# quadcopter_tawfic.net
KiCad netlist of a schematic drawn in EAGLE
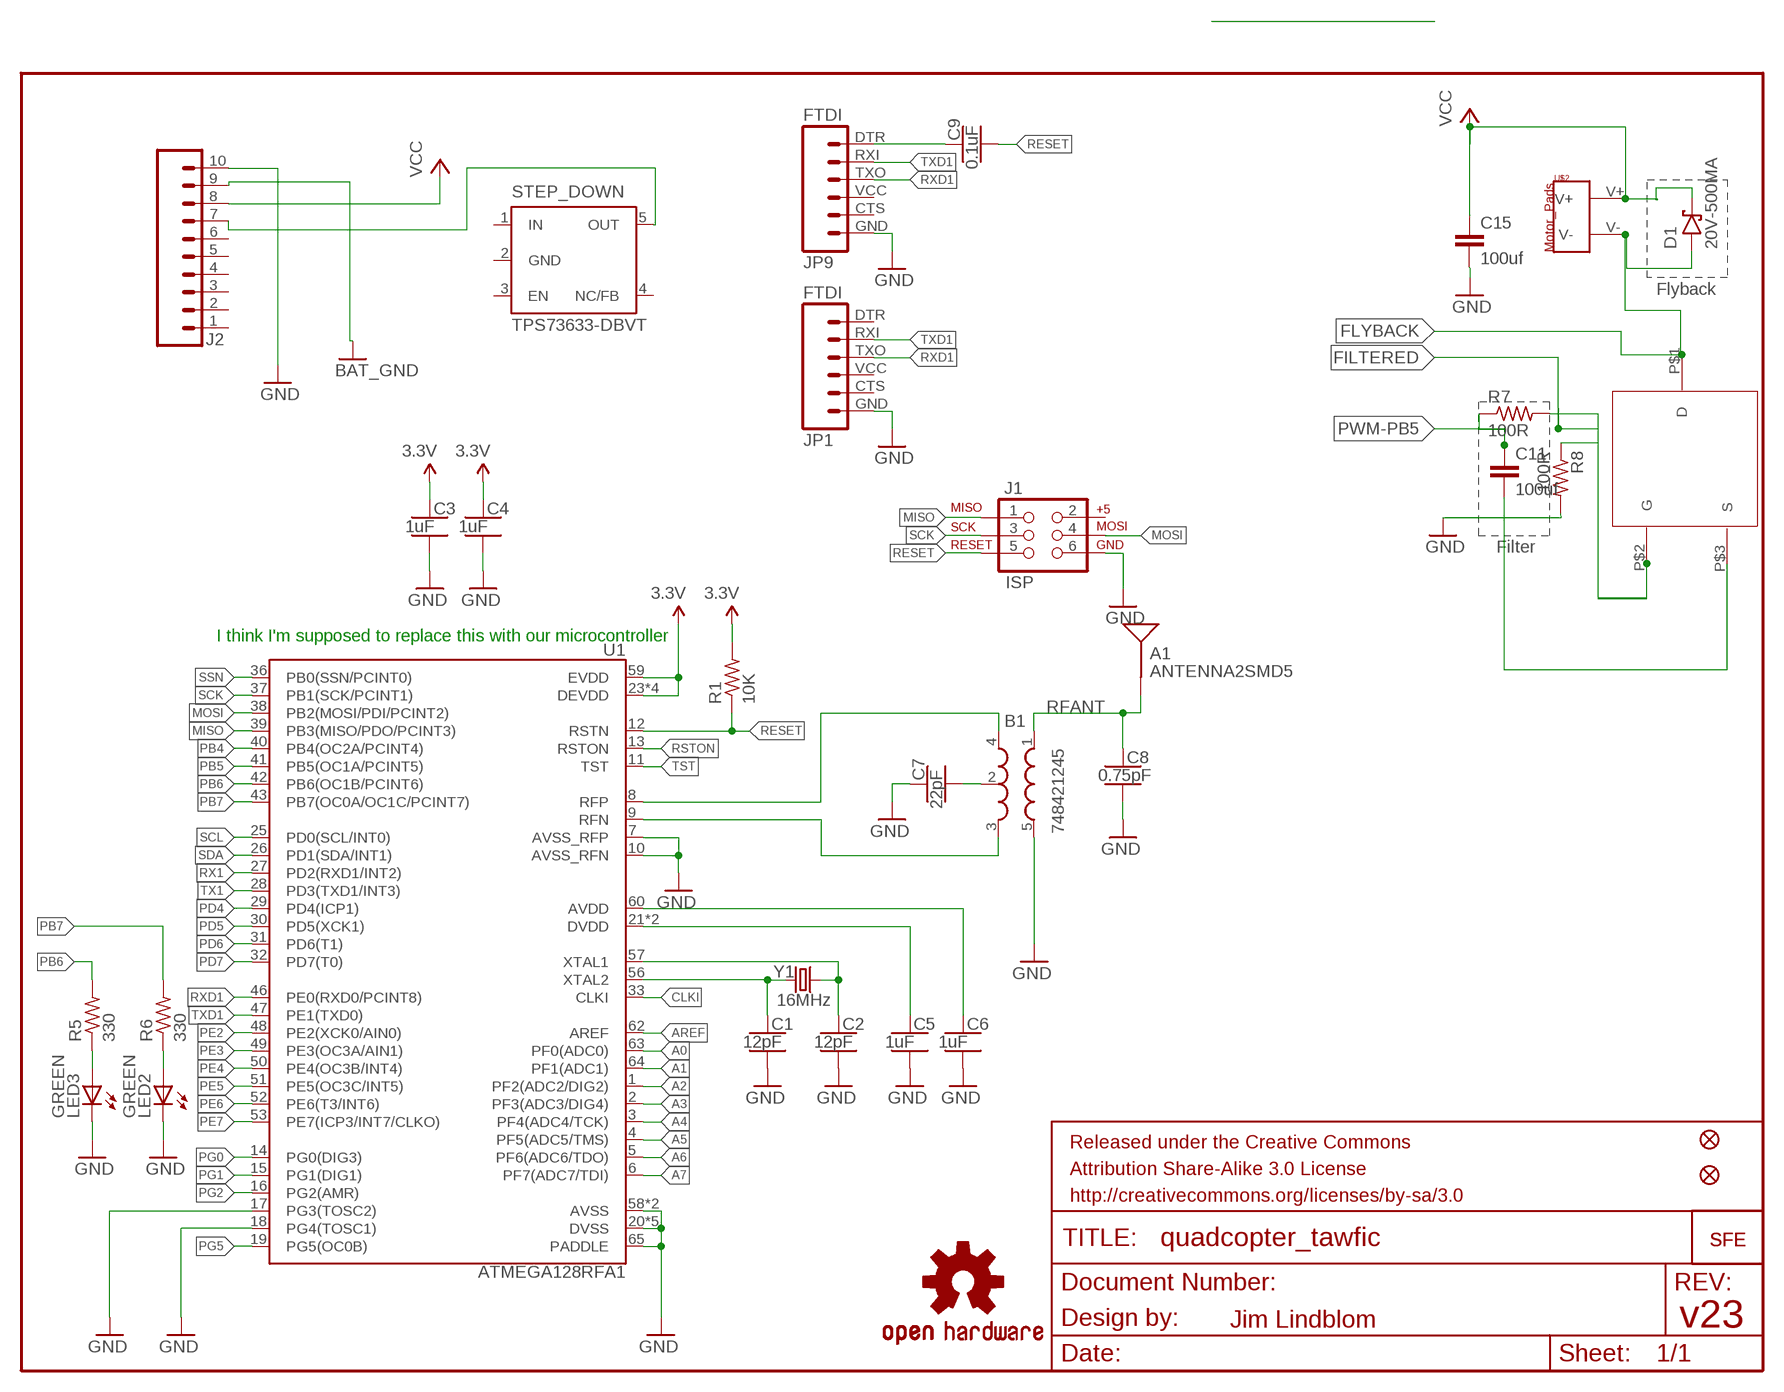
[diagram p0: schematic, sheet 1]

(export (version "E")
  (design (tool "Eeschema 10.0.6"))
  (components
    (comp (ref "A1")
      (value "ANTENNA2SMD5")
      (footprint "eagle-import:ANTENNA-CHIP5")
      (libsource (lib "eagle-import") (part "ANTENNA2SMD5"))
    )
    (comp (ref "B1")
      (value "748421245")
      (footprint "eagle-import:BALUN")
      (libsource (lib "eagle-import") (part "BALUN0805"))
    )
    (comp (ref "C1")
      (value "12pF")
      (footprint "eagle-import:CAPC2012X140_HS")
      (fields
        (field (name "MFR") "Murata Electronics North America")
        (field (name "MPN") "GRM21A5C2E120JW01D")
      )
      (libsource (lib "eagle-import") (part "CAPACITOR-NP_SMD-2012-0805_CERAMIC-12PF"))
    )
    (comp (ref "C2")
      (value "12pF")
      (footprint "eagle-import:CAPC2012X140_HS")
      (fields
        (field (name "MFR") "Murata Electronics North America")
        (field (name "MPN") "GRM21A5C2E120JW01D")
      )
      (libsource (lib "eagle-import") (part "CAPACITOR-NP_SMD-2012-0805_CERAMIC-12PF"))
    )
    (comp (ref "C3")
      (value "1uF")
      (footprint "eagle-import:CAPC2012X140_HS")
      (fields
        (field (name "MFR") "Murata Electronics North America")
        (field (name "MPN") "GRM21BR71H105KA12L")
      )
      (libsource (lib "eagle-import") (part "CAPACITOR-NP_SMD-2012-0805_CERAMIC-1UF"))
    )
    (comp (ref "C4")
      (value "1uF")
      (footprint "eagle-import:CAPC2012X140_HS")
      (fields
        (field (name "MFR") "Murata Electronics North America")
        (field (name "MPN") "GRM21BR71H105KA12L")
      )
      (libsource (lib "eagle-import") (part "CAPACITOR-NP_SMD-2012-0805_CERAMIC-1UF"))
    )
    (comp (ref "C5")
      (value "1uF")
      (footprint "eagle-import:CAPC2012X140_HS")
      (fields
        (field (name "MFR") "Murata Electronics North America")
        (field (name "MPN") "GRM21BR71H105KA12L")
      )
      (libsource (lib "eagle-import") (part "CAPACITOR-NP_SMD-2012-0805_CERAMIC-1UF"))
    )
    (comp (ref "C6")
      (value "1uF")
      (footprint "eagle-import:CAPC2012X140_HS")
      (fields
        (field (name "MFR") "Murata Electronics North America")
        (field (name "MPN") "GRM21BR71H105KA12L")
      )
      (libsource (lib "eagle-import") (part "CAPACITOR-NP_SMD-2012-0805_CERAMIC-1UF"))
    )
    (comp (ref "C7")
      (value "22pF")
      (footprint "eagle-import:CAPC2012X140_HS")
      (fields
        (field (name "MFR") "Murata Electronics North America")
        (field (name "MPN") "GRM21A5C2E220JW01D")
      )
      (libsource (lib "eagle-import") (part "CAPACITOR-NP_SMD-2012-0805_CERAMIC-22PF"))
    )
    (comp (ref "C8")
      (value "0.75pF")
      (footprint "eagle-import:CAPC2012X140_HS")
      (fields
        (field (name "MFR") "Murata Electronics North America")
        (field (name "MPN") "GQM2195C2AR75CB01D")
      )
      (libsource (lib "eagle-import") (part "CAPACITOR-NP_SMD-2012-0805_CERAMIC-0.75PF"))
    )
    (comp (ref "C9")
      (value "0.1uF")
      (footprint "eagle-import:CAPC2012X140_HS")
      (fields
        (field (name "MFR") "Murata Electronics North America")
        (field (name "MPN") "GRM21BR71H104KA01L")
      )
      (libsource (lib "eagle-import") (part "CAPACITOR-NP_SMD-2012-0805_CERAMIC-0.1UF"))
    )
    (comp (ref "C11")
      (value "100uf")
      (footprint "eagle-import:C10B4")
      (libsource (lib "eagle-import") (part "C10/4"))
    )
    (comp (ref "C15")
      (value "100uf")
      (footprint "eagle-import:C10B4")
      (libsource (lib "eagle-import") (part "C10/4"))
    )
    (comp (ref "D1")
      (value "20V-500MA")
      (footprint "eagle-import:SOD3716X135_HS")
      (fields
        (field (name "MFR") "Toshiba Semiconductor and Storage")
        (field (name "MPN") "CRS08(TE85L,Q,M)")
      )
      (libsource (lib "eagle-import") (part "DIODE-SCHOTTKY_SMD-SOD123-360MV"))
    )
    (comp (ref "FID1")
      (value "FIDUCIALUFIDUCIAL")
      (footprint "eagle-import:MICRO-FIDUCIAL")
      (libsource (lib "eagle-import") (part "FIDUCIALUFIDUCIAL"))
    )
    (comp (ref "FID2")
      (value "FIDUCIALUFIDUCIAL")
      (footprint "eagle-import:MICRO-FIDUCIAL")
      (libsource (lib "eagle-import") (part "FIDUCIALUFIDUCIAL"))
    )
    (comp (ref "J1")
      (value "ISP")
      (footprint "eagle-import:2X3-NS")
      (libsource (lib "eagle-import") (part "AVR_SPI_PRG_6NS"))
    )
    (comp (ref "J2")
      (value "SIP-10_TH-254X10-1")
      (footprint "eagle-import:HDRV10W63P254_10X1_2540X254H838_HS")
      (fields (field (name "MFR") "Amphenol FCI") (field (name "MPN") "68000-110HLF"))
      (libsource (lib "eagle-import") (part "SIP-10_TH-254X10-1"))
    )
    (comp (ref "JP1")
      (value "FTDI")
      (footprint "eagle-import:FTDI_BASIC")
      (libsource (lib "eagle-import") (part "FTDI_BASICPTH"))
    )
    (comp (ref "JP4")
      (value "LOGO-SFENEW")
      (footprint "eagle-import:SFE-NEW-WEBLOGO")
      (libsource (lib "eagle-import") (part "LOGO-SFENEW"))
    )
    (comp (ref "JP9")
      (value "FTDI")
      (footprint "eagle-import:FTDI_BASIC")
      (libsource (lib "eagle-import") (part "FTDI_BASICPTH"))
    )
    (comp (ref "JP10")
      (value "LOGO-SFENEW")
      (footprint "eagle-import:SFE-NEW-WEBLOGO")
      (libsource (lib "eagle-import") (part "LOGO-SFENEW"))
    )
    (comp (ref "LED2")
      (value "GREEN")
      (footprint "eagle-import:LED-0603")
      (libsource (lib "eagle-import") (part "LED0603"))
    )
    (comp (ref "LED3")
      (value "GREEN")
      (footprint "eagle-import:LED-0603")
      (libsource (lib "eagle-import") (part "LED0603"))
    )
    (comp (ref "Q2")
      (value "MOSFET-SI2302CDS-T1-E3")
      (footprint "eagle-import:MOSFET")
      (libsource (lib "eagle-import") (part "MOSFET-SI2302CDS-T1-E3"))
    )
    (comp (ref "R1")
      (value "10K")
      (footprint "eagle-import:RESC2012X60_HS")
      (fields (field (name "MFR") "Yageo") (field (name "MPN") "RC0805JR-0710KL"))
      (libsource (lib "eagle-import") (part "RESISTOR_SMD-2012-0805-10K"))
    )
    (comp (ref "R5")
      (value "330")
      (footprint "eagle-import:RESC2012X60_HS")
      (fields (field (name "MFR") "Yageo") (field (name "MPN") "RC0805JR-07330RL"))
      (libsource (lib "eagle-import") (part "RESISTOR_SMD-2012-0805-330"))
    )
    (comp (ref "R6")
      (value "330")
      (footprint "eagle-import:RESC2012X60_HS")
      (fields (field (name "MFR") "Yageo") (field (name "MPN") "RC0805JR-07330RL"))
      (libsource (lib "eagle-import") (part "RESISTOR_SMD-2012-0805-330"))
    )
    (comp (ref "R7")
      (value "100R")
      (footprint "eagle-import:R0805")
      (libsource (lib "eagle-import") (part "R-US_R0805"))
    )
    (comp (ref "R8")
      (value "100R")
      (footprint "eagle-import:R0805")
      (libsource (lib "eagle-import") (part "R-US_R0805"))
    )
    (comp (ref "STEP_DOWN")
      (value "TPS73633-DBVT")
      (footprint "eagle-import:SOT23-DBV")
      (fields (field (name "MFR") "Texas Instruments") (field (name "MPN") "LP3985IM5X-3.0/NOPB"))
      (libsource (lib "eagle-import") (part "TPS73633-DBVT"))
    )
    (comp (ref "U$1")
      (value "OSHW-LOGOS")
      (footprint "eagle-import:OSHW-LOGO-S")
      (libsource (lib "eagle-import") (part "OSHW-LOGOS"))
    )
    (comp (ref "U$2")
      (value "MOTOR_PADS")
      (footprint "eagle-import:MOTOR_PADS")
      (fields (field (name "MFR") "NA"))
      (libsource (lib "eagle-import") (part "MOTOR_PADS"))
    )
    (comp (ref "U1")
      (value "ATMEGA128RFA1")
      (footprint "eagle-import:QFN-64")
      (libsource (lib "eagle-import") (part "ATMEGA128RFA1"))
    )
    (comp (ref "Y1")
      (value "16MHz")
      (footprint "eagle-import:CRYSTAL-SMD-5X3")
      (libsource (lib "eagle-import") (part "CRYSTAL5X3"))
    )
  )
  (nets
    (net (code "1") (name "/RFANT") (class "Default")
      (node (ref "A1") (pin "FEED") (pinfunction "SIGNAL_FEED") (pintype "bidirectional"))
      (node (ref "B1") (pin "1") (pinfunction "IN_1") (pintype "bidirectional"))
      (node (ref "C8") (pin "1") (pinfunction "1_1") (pintype "passive"))
    )
    (net (code "2") (name "3.3V") (class "Default")
      (node (ref "C3") (pin "1") (pinfunction "1_1") (pintype "passive"))
      (node (ref "C4") (pin "1") (pinfunction "1_1") (pintype "passive"))
      (node (ref "R1") (pin "2") (pinfunction "2_2") (pintype "passive"))
      (node (ref "U1") (pin "23") (pinfunction "DEVDD_23") (pintype "bidirectional"))
      (node (ref "U1") (pin "34") (pinfunction "DEVDD_34") (pintype "bidirectional"))
      (node (ref "U1") (pin "44") (pinfunction "DEVDD_44") (pintype "bidirectional"))
      (node (ref "U1") (pin "54") (pinfunction "DEVDD_54") (pintype "bidirectional"))
      (node (ref "U1") (pin "59") (pinfunction "EVDD_59") (pintype "bidirectional"))
    )
    (net (code "3") (name "A0") (class "Default")
      (node (ref "U1") (pin "63") (pinfunction "PF0(ADC0)_63") (pintype "bidirectional"))
    )
    (net (code "4") (name "A1") (class "Default")
      (node (ref "U1") (pin "64") (pinfunction "PF1(ADC1)_64") (pintype "bidirectional"))
    )
    (net (code "5") (name "A2") (class "Default")
      (node (ref "U1") (pin "1") (pinfunction "PF2(ADC2/DIG2)_1") (pintype "bidirectional"))
    )
    (net (code "6") (name "A3") (class "Default")
      (node (ref "U1") (pin "2") (pinfunction "PF3(ADC3/DIG4)_2") (pintype "bidirectional"))
    )
    (net (code "7") (name "A4") (class "Default")
      (node (ref "U1") (pin "3") (pinfunction "PF4(ADC4/TCK)_3") (pintype "bidirectional"))
    )
    (net (code "8") (name "A5") (class "Default")
      (node (ref "U1") (pin "4") (pinfunction "PF5(ADC5/TMS)_4") (pintype "bidirectional"))
    )
    (net (code "9") (name "A6") (class "Default")
      (node (ref "U1") (pin "5") (pinfunction "PF6(ADC6/TDO)_5") (pintype "bidirectional"))
    )
    (net (code "10") (name "A7") (class "Default")
      (node (ref "U1") (pin "6") (pinfunction "PF7(ADC7/TDI)_6") (pintype "bidirectional"))
    )
    (net (code "11") (name "AREF") (class "Default")
      (node (ref "U1") (pin "62") (pinfunction "AREF_62") (pintype "bidirectional"))
    )
    (net (code "12") (name "BAT_GND") (class "Default")
      (node (ref "J2") (pin "9") (pinfunction "9_9") (pintype "passive"))
    )
    (net (code "13") (name "CLKI") (class "Default")
      (node (ref "U1") (pin "33") (pinfunction "CLKI_33") (pintype "bidirectional"))
    )
    (net (code "14") (name "FILTERED") (class "Default")
      (node (ref "Q2") (pin "P$2") (pinfunction "G_P$2") (pintype "power_in"))
      (node (ref "R7") (pin "2") (pinfunction "2_2") (pintype "passive"))
      (node (ref "R8") (pin "1") (pinfunction "1_1") (pintype "passive"))
    )
    (net (code "15") (name "FLYBACK") (class "Default")
      (node (ref "D1") (pin "A") (pinfunction "A_A") (pintype "passive"))
      (node (ref "Q2") (pin "P$1") (pinfunction "D_P$1") (pintype "bidirectional"))
      (node (ref "U$2") (pin "V-") (pinfunction "V-_V-") (pintype "bidirectional"))
    )
    (net (code "16") (name "GND") (class "Default")
      (node (ref "B1") (pin "5") (pinfunction "GND_5") (pintype "bidirectional"))
      (node (ref "C1") (pin "2") (pinfunction "2_2") (pintype "passive"))
      (node (ref "C15") (pin "2") (pinfunction "2_2") (pintype "passive"))
      (node (ref "C2") (pin "2") (pinfunction "2_2") (pintype "passive"))
      (node (ref "C3") (pin "2") (pinfunction "2_2") (pintype "passive"))
      (node (ref "C4") (pin "2") (pinfunction "2_2") (pintype "passive"))
      (node (ref "C5") (pin "2") (pinfunction "2_2") (pintype "passive"))
      (node (ref "C6") (pin "2") (pinfunction "2_2") (pintype "passive"))
      (node (ref "C7") (pin "1") (pinfunction "1_1") (pintype "passive"))
      (node (ref "C8") (pin "2") (pinfunction "2_2") (pintype "passive"))
      (node (ref "J1") (pin "6") (pinfunction "6_6") (pintype "passive"))
      (node (ref "J2") (pin "10") (pinfunction "10_10") (pintype "passive"))
      (node (ref "JP1") (pin "GND") (pinfunction "6_GND") (pintype "passive"))
      (node (ref "JP9") (pin "GND") (pinfunction "6_GND") (pintype "passive"))
      (node (ref "LED2") (pin "C") (pinfunction "C_C") (pintype "passive"))
      (node (ref "LED3") (pin "C") (pinfunction "C_C") (pintype "passive"))
      (node (ref "R8") (pin "2") (pinfunction "2_2") (pintype "passive"))
      (node (ref "U1") (pin "10") (pinfunction "AVSS_RFN_10") (pintype "bidirectional"))
      (node (ref "U1") (pin "17") (pinfunction "PG3(TOSC2)_17") (pintype "bidirectional"))
      (node (ref "U1") (pin "18") (pinfunction "PG4(TOSC1)_18") (pintype "bidirectional"))
      (node (ref "U1") (pin "20") (pinfunction "DVSS_20") (pintype "bidirectional"))
      (node (ref "U1") (pin "24") (pinfunction "DVSS_24") (pintype "bidirectional"))
      (node (ref "U1") (pin "35") (pinfunction "DVSS_35") (pintype "bidirectional"))
      (node (ref "U1") (pin "45") (pinfunction "DVSS_45") (pintype "bidirectional"))
      (node (ref "U1") (pin "55") (pinfunction "DVSS_55") (pintype "bidirectional"))
      (node (ref "U1") (pin "58") (pinfunction "AVSS_58") (pintype "bidirectional"))
      (node (ref "U1") (pin "61") (pinfunction "AVSS_61") (pintype "bidirectional"))
      (node (ref "U1") (pin "65") (pinfunction "PADDLE_65") (pintype "bidirectional"))
      (node (ref "U1") (pin "7") (pinfunction "AVSS_RFP_7") (pintype "bidirectional"))
    )
    (net (code "17") (name "MISO") (class "Default")
      (node (ref "J1") (pin "1") (pinfunction "1_1") (pintype "passive"))
      (node (ref "U1") (pin "39") (pinfunction "PB3(MISO/PDO/PCINT3)_39") (pintype "bidirectional"))
    )
    (net (code "18") (name "MOSI") (class "Default")
      (node (ref "J1") (pin "4") (pinfunction "4_4") (pintype "passive"))
      (node (ref "U1") (pin "38") (pinfunction "PB2(MOSI/PDI/PCINT2)_38") (pintype "bidirectional"))
    )
    (net (code "19") (name "Net-(B1-GND-Pad2)") (class "Default")
      (node (ref "B1") (pin "2") (pinfunction "GND_2") (pintype "bidirectional"))
      (node (ref "C7") (pin "2") (pinfunction "2_2") (pintype "passive"))
    )
    (net (code "20") (name "Net-(B1-OUT1)") (class "Default")
      (node (ref "B1") (pin "4") (pinfunction "OUT1_4") (pintype "bidirectional"))
      (node (ref "U1") (pin "8") (pinfunction "RFP_8") (pintype "bidirectional"))
    )
    (net (code "21") (name "Net-(B1-OUT2)") (class "Default")
      (node (ref "B1") (pin "3") (pinfunction "OUT2_3") (pintype "bidirectional"))
      (node (ref "U1") (pin "9") (pinfunction "RFN_9") (pintype "bidirectional"))
    )
    (net (code "22") (name "Net-(C5-Pad1)") (class "Default")
      (node (ref "C5") (pin "1") (pinfunction "1_1") (pintype "passive"))
      (node (ref "U1") (pin "21") (pinfunction "DVDD_21") (pintype "bidirectional"))
      (node (ref "U1") (pin "22") (pinfunction "DVDD_22") (pintype "bidirectional"))
    )
    (net (code "23") (name "Net-(JP9-1)") (class "Default")
      (node (ref "C9") (pin "1") (pinfunction "1_1") (pintype "passive"))
      (node (ref "JP9") (pin "DTR") (pinfunction "1_DTR") (pintype "passive"))
    )
    (net (code "24") (name "Net-(LED2-PadA)") (class "Default")
      (node (ref "LED2") (pin "A") (pinfunction "A_A") (pintype "passive"))
      (node (ref "R6") (pin "1") (pinfunction "1_1") (pintype "passive"))
    )
    (net (code "25") (name "Net-(LED3-PadA)") (class "Default")
      (node (ref "LED3") (pin "A") (pinfunction "A_A") (pintype "passive"))
      (node (ref "R5") (pin "1") (pinfunction "1_1") (pintype "passive"))
    )
    (net (code "26") (name "Net-(Q2-S)") (class "Default")
      (node (ref "C11") (pin "2") (pinfunction "2_2") (pintype "passive"))
      (node (ref "Q2") (pin "P$3") (pinfunction "S_P$3") (pintype "bidirectional"))
    )
    (net (code "27") (name "Net-(STEP_DOWN-OUT)") (class "Default")
      (node (ref "J2") (pin "7") (pinfunction "7_7") (pintype "passive"))
      (node (ref "STEP_DOWN") (pin "5") (pinfunction "OUT_5") (pintype "passive"))
    )
    (net (code "28") (name "Net-(U1-AVDD)") (class "Default")
      (node (ref "C6") (pin "1") (pinfunction "1_1") (pintype "passive"))
      (node (ref "U1") (pin "60") (pinfunction "AVDD_60") (pintype "bidirectional"))
    )
    (net (code "29") (name "Net-(U1-XTAL1)") (class "Default")
      (node (ref "C2") (pin "1") (pinfunction "1_1") (pintype "passive"))
      (node (ref "U1") (pin "57") (pinfunction "XTAL1_57") (pintype "bidirectional"))
      (node (ref "Y1") (pin "3") (pinfunction "2_3") (pintype "passive"))
    )
    (net (code "30") (name "Net-(U1-XTAL2)") (class "Default")
      (node (ref "C1") (pin "1") (pinfunction "1_1") (pintype "passive"))
      (node (ref "U1") (pin "56") (pinfunction "XTAL2_56") (pintype "bidirectional"))
      (node (ref "Y1") (pin "1") (pinfunction "1_1") (pintype "passive"))
    )
    (net (code "31") (name "PB4") (class "Default")
      (node (ref "U1") (pin "40") (pinfunction "PB4(OC2A/PCINT4)_40") (pintype "bidirectional"))
    )
    (net (code "32") (name "PB5") (class "Default")
      (node (ref "U1") (pin "41") (pinfunction "PB5(OC1A/PCINT5)_41") (pintype "bidirectional"))
    )
    (net (code "33") (name "PB6") (class "Default")
      (node (ref "R5") (pin "2") (pinfunction "2_2") (pintype "passive"))
      (node (ref "U1") (pin "42") (pinfunction "PB6(OC1B/PCINT6)_42") (pintype "bidirectional"))
    )
    (net (code "34") (name "PB7") (class "Default")
      (node (ref "R6") (pin "2") (pinfunction "2_2") (pintype "passive"))
      (node (ref "U1") (pin "43") (pinfunction "PB7(OC0A/OC1C/PCINT7)_43") (pintype "bidirectional"))
    )
    (net (code "35") (name "PD4") (class "Default")
      (node (ref "U1") (pin "29") (pinfunction "PD4(ICP1)_29") (pintype "bidirectional"))
    )
    (net (code "36") (name "PD5") (class "Default")
      (node (ref "U1") (pin "30") (pinfunction "PD5(XCK1)_30") (pintype "bidirectional"))
    )
    (net (code "37") (name "PD6") (class "Default")
      (node (ref "U1") (pin "31") (pinfunction "PD6(T1)_31") (pintype "bidirectional"))
    )
    (net (code "38") (name "PD7") (class "Default")
      (node (ref "U1") (pin "32") (pinfunction "PD7(T0)_32") (pintype "bidirectional"))
    )
    (net (code "39") (name "PE2") (class "Default")
      (node (ref "U1") (pin "48") (pinfunction "PE2(XCK0/AIN0)_48") (pintype "bidirectional"))
    )
    (net (code "40") (name "PE3") (class "Default")
      (node (ref "U1") (pin "49") (pinfunction "PE3(OC3A/AIN1)_49") (pintype "bidirectional"))
    )
    (net (code "41") (name "PE4") (class "Default")
      (node (ref "U1") (pin "50") (pinfunction "PE4(OC3B/INT4)_50") (pintype "bidirectional"))
    )
    (net (code "42") (name "PE5") (class "Default")
      (node (ref "U1") (pin "51") (pinfunction "PE5(OC3C/INT5)_51") (pintype "bidirectional"))
    )
    (net (code "43") (name "PE6") (class "Default")
      (node (ref "U1") (pin "52") (pinfunction "PE6(T3/INT6)_52") (pintype "bidirectional"))
    )
    (net (code "44") (name "PE7") (class "Default")
      (node (ref "U1") (pin "53") (pinfunction "PE7(ICP3/INT7/CLKO)_53") (pintype "bidirectional"))
    )
    (net (code "45") (name "PG0") (class "Default")
      (node (ref "U1") (pin "14") (pinfunction "PG0(DIG3)_14") (pintype "bidirectional"))
    )
    (net (code "46") (name "PG1") (class "Default")
      (node (ref "U1") (pin "15") (pinfunction "PG1(DIG1)_15") (pintype "bidirectional"))
    )
    (net (code "47") (name "PG2") (class "Default")
      (node (ref "U1") (pin "16") (pinfunction "PG2(AMR)_16") (pintype "bidirectional"))
    )
    (net (code "48") (name "PG5") (class "Default")
      (node (ref "U1") (pin "19") (pinfunction "PG5(OC0B)_19") (pintype "bidirectional"))
    )
    (net (code "49") (name "PWM-PB5") (class "Default")
      (node (ref "C11") (pin "1") (pinfunction "1_1") (pintype "passive"))
      (node (ref "R7") (pin "1") (pinfunction "1_1") (pintype "passive"))
    )
    (net (code "50") (name "RESET") (class "Default")
      (node (ref "C9") (pin "2") (pinfunction "2_2") (pintype "passive"))
      (node (ref "J1") (pin "5") (pinfunction "5_5") (pintype "passive"))
      (node (ref "R1") (pin "1") (pinfunction "1_1") (pintype "passive"))
      (node (ref "U1") (pin "12") (pinfunction "RSTN_12") (pintype "bidirectional"))
    )
    (net (code "51") (name "RSTON") (class "Default")
      (node (ref "U1") (pin "13") (pinfunction "RSTON_13") (pintype "bidirectional"))
    )
    (net (code "52") (name "RX1") (class "Default")
      (node (ref "U1") (pin "27") (pinfunction "PD2(RXD1/INT2)_27") (pintype "bidirectional"))
    )
    (net (code "53") (name "RXD1") (class "Default")
      (node (ref "JP1") (pin "TXO") (pinfunction "3_TXO") (pintype "passive"))
      (node (ref "JP9") (pin "TXO") (pinfunction "3_TXO") (pintype "passive"))
      (node (ref "U1") (pin "46") (pinfunction "PE0(RXD0/PCINT8)_46") (pintype "bidirectional"))
    )
    (net (code "54") (name "SCK") (class "Default")
      (node (ref "J1") (pin "3") (pinfunction "3_3") (pintype "passive"))
      (node (ref "U1") (pin "37") (pinfunction "PB1(SCK/PCINT1)_37") (pintype "bidirectional"))
    )
    (net (code "55") (name "SCL") (class "Default")
      (node (ref "U1") (pin "25") (pinfunction "PD0(SCL/INT0)_25") (pintype "bidirectional"))
    )
    (net (code "56") (name "SDA") (class "Default")
      (node (ref "U1") (pin "26") (pinfunction "PD1(SDA/INT1)_26") (pintype "bidirectional"))
    )
    (net (code "57") (name "SSN") (class "Default")
      (node (ref "U1") (pin "36") (pinfunction "PB0(SSN/PCINT0)_36") (pintype "bidirectional"))
    )
    (net (code "58") (name "TST") (class "Default")
      (node (ref "U1") (pin "11") (pinfunction "TST_11") (pintype "bidirectional"))
    )
    (net (code "59") (name "TX1") (class "Default")
      (node (ref "U1") (pin "28") (pinfunction "PD3(TXD1/INT3)_28") (pintype "bidirectional"))
    )
    (net (code "60") (name "TXD1") (class "Default")
      (node (ref "JP1") (pin "RXI") (pinfunction "2_RXI") (pintype "passive"))
      (node (ref "JP9") (pin "RXI") (pinfunction "2_RXI") (pintype "passive"))
      (node (ref "U1") (pin "47") (pinfunction "PE1(TXD0)_47") (pintype "bidirectional"))
    )
    (net (code "61") (name "VCC") (class "Default")
      (node (ref "C15") (pin "1") (pinfunction "1_1") (pintype "passive"))
      (node (ref "D1") (pin "C") (pinfunction "C_C") (pintype "passive"))
      (node (ref "J2") (pin "8") (pinfunction "8_8") (pintype "passive"))
      (node (ref "U$2") (pin "V+") (pinfunction "V+_V+") (pintype "bidirectional"))
    )
    (net (code "62") (name "unconnected-(J1-Pad2)") (class "Default")
      (node (ref "J1") (pin "2") (pinfunction "2_2") (pintype "passive"))
    )
    (net (code "63") (name "unconnected-(J2-Pad1)") (class "Default")
      (node (ref "J2") (pin "1") (pinfunction "1_1") (pintype "passive"))
    )
    (net (code "64") (name "unconnected-(J2-Pad2)") (class "Default")
      (node (ref "J2") (pin "2") (pinfunction "2_2") (pintype "passive"))
    )
    (net (code "65") (name "unconnected-(J2-Pad3)") (class "Default")
      (node (ref "J2") (pin "3") (pinfunction "3_3") (pintype "passive"))
    )
    (net (code "66") (name "unconnected-(J2-Pad4)") (class "Default")
      (node (ref "J2") (pin "4") (pinfunction "4_4") (pintype "passive"))
    )
    (net (code "67") (name "unconnected-(J2-Pad5)") (class "Default")
      (node (ref "J2") (pin "5") (pinfunction "5_5") (pintype "passive"))
    )
    (net (code "68") (name "unconnected-(J2-Pad6)") (class "Default")
      (node (ref "J2") (pin "6") (pinfunction "6_6") (pintype "passive"))
    )
    (net (code "69") (name "unconnected-(JP1-1-PadDTR)") (class "Default")
      (node (ref "JP1") (pin "DTR") (pinfunction "1_DTR") (pintype "passive"))
    )
    (net (code "70") (name "unconnected-(JP1-4-PadVCC)") (class "Default")
      (node (ref "JP1") (pin "VCC") (pinfunction "4_VCC") (pintype "passive"))
    )
    (net (code "71") (name "unconnected-(JP1-5-PadCTS)") (class "Default")
      (node (ref "JP1") (pin "CTS") (pinfunction "5_CTS") (pintype "passive"))
    )
    (net (code "72") (name "unconnected-(JP9-4-PadVCC)") (class "Default")
      (node (ref "JP9") (pin "VCC") (pinfunction "4_VCC") (pintype "passive"))
    )
    (net (code "73") (name "unconnected-(JP9-5-PadCTS)") (class "Default")
      (node (ref "JP9") (pin "CTS") (pinfunction "5_CTS") (pintype "passive"))
    )
    (net (code "74") (name "unconnected-(STEP_DOWN-EN-Pad3)") (class "Default")
      (node (ref "STEP_DOWN") (pin "3") (pinfunction "EN_3") (pintype "input"))
    )
    (net (code "75") (name "unconnected-(STEP_DOWN-GND-Pad2)") (class "Default")
      (node (ref "STEP_DOWN") (pin "2") (pinfunction "GND_2") (pintype "input"))
    )
    (net (code "76") (name "unconnected-(STEP_DOWN-IN-Pad1)") (class "Default")
      (node (ref "STEP_DOWN") (pin "1") (pinfunction "IN_1") (pintype "input"))
    )
    (net (code "77") (name "unconnected-(STEP_DOWN-NC{slash}FB-Pad4)") (class "Default")
      (node (ref "STEP_DOWN") (pin "4") (pinfunction "NC/FB_4") (pintype "passive"))
    )
  )
)
